# DAMPOWER.net
KiCad netlist of a schematic drawn in EAGLE
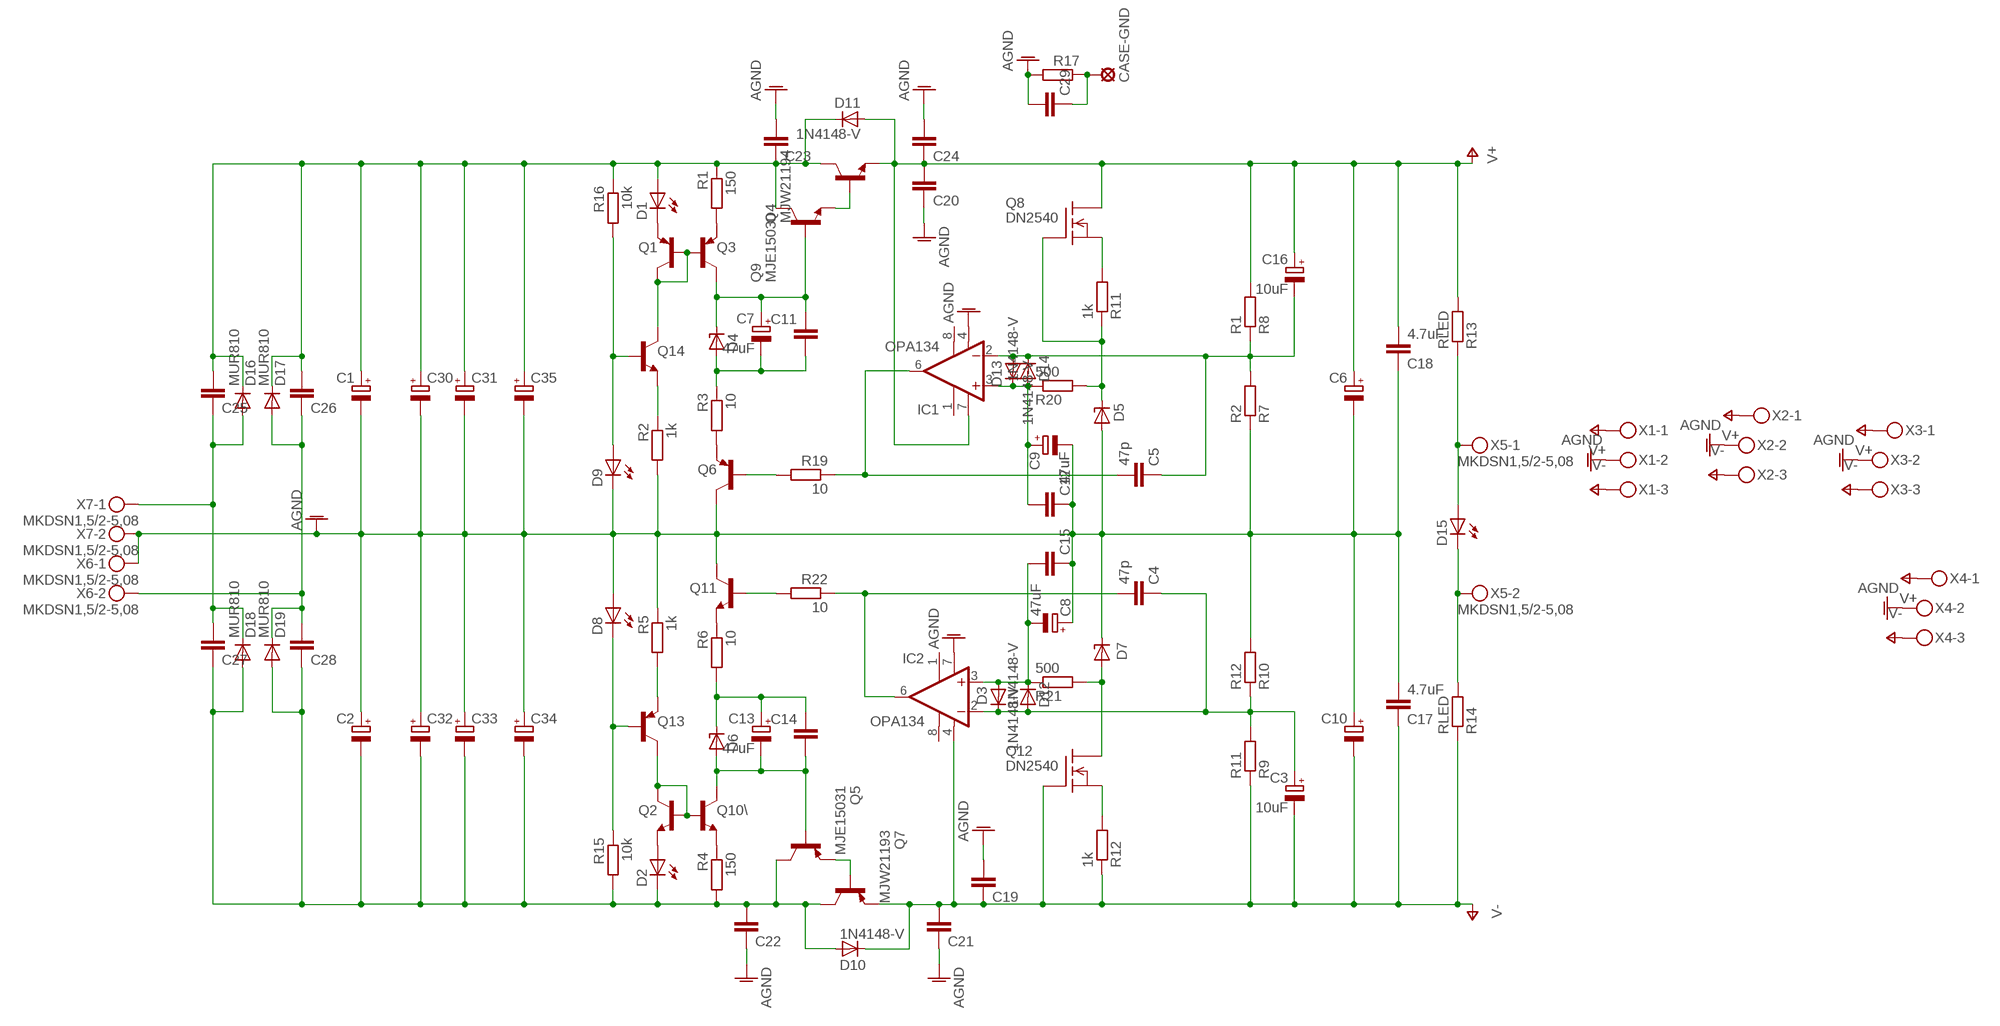
[diagram p0: schematic, sheet 1]
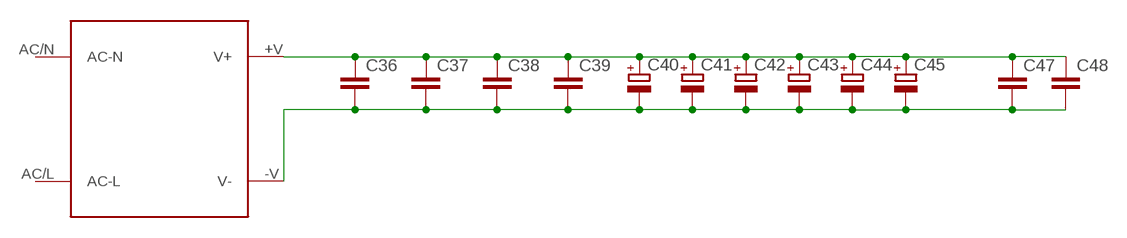
[diagram p1: schematic, sheet 2]
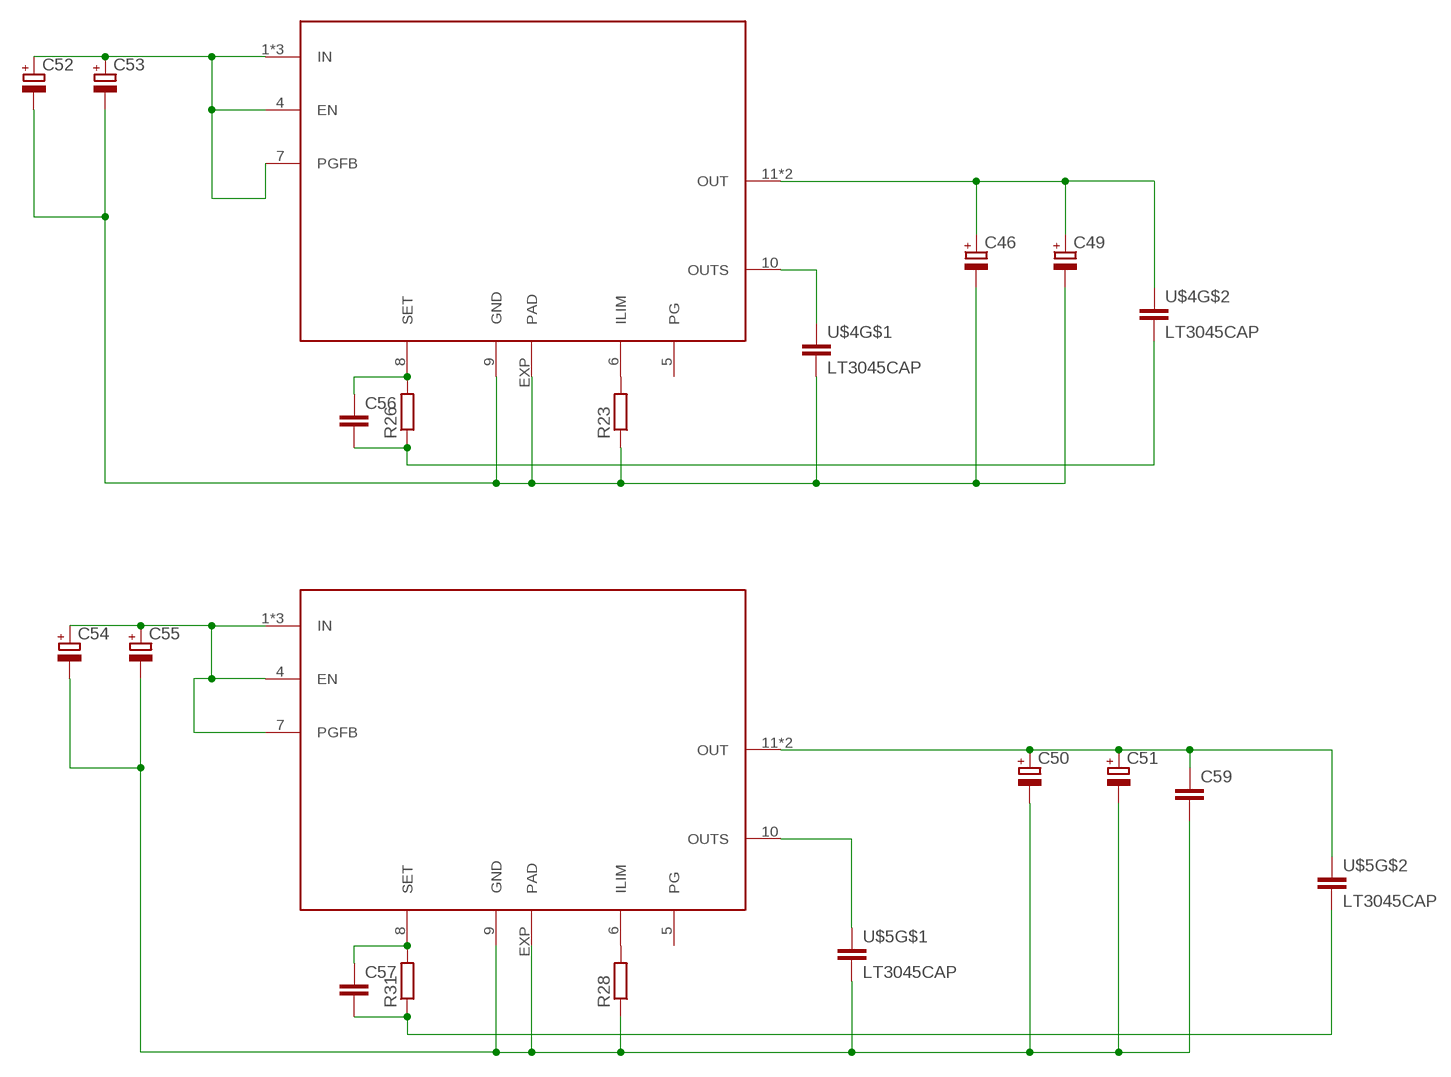
[diagram p2: schematic, sheet 3]

(export (version "E")
  (design (tool "Eeschema 10.0.6"))
  (components
    (comp (ref "C1")
      (value "CPOL-EUE10-35")
      (footprint "eagle-import:EB35D")
      (libsource (lib "eagle-import") (part "CPOL-EUE10-35"))
    )
    (comp (ref "C2")
      (value "CPOL-EUE10-35")
      (footprint "eagle-import:EB35D")
      (libsource (lib "eagle-import") (part "CPOL-EUE10-35"))
    )
    (comp (ref "C3")
      (value "10uF")
      (footprint "eagle-import:E5-8,5")
      (libsource (lib "eagle-import") (part "CPOL-EUE5-8.5"))
    )
    (comp (ref "C4")
      (value "47p")
      (footprint "eagle-import:C025_050-025X075")
      (libsource (lib "eagle-import") (part "C-EU025_050-025X075"))
    )
    (comp (ref "C5")
      (value "47p")
      (footprint "eagle-import:C025_050-025X075")
      (libsource (lib "eagle-import") (part "C-EU025_050-025X075"))
    )
    (comp (ref "C6")
      (value "CPOL-EUE7.5-18")
      (footprint "eagle-import:E7,5-18")
      (libsource (lib "eagle-import") (part "CPOL-EUE7.5-18"))
    )
    (comp (ref "C7")
      (value "47uF")
      (footprint "eagle-import:E5-8,5")
      (libsource (lib "eagle-import") (part "CPOL-EUE5-8.5"))
    )
    (comp (ref "C8")
      (value "47uF")
      (footprint "eagle-import:E5-8,5")
      (libsource (lib "eagle-import") (part "CPOL-EUE5-8.5"))
    )
    (comp (ref "C9")
      (value "47uF")
      (footprint "eagle-import:E5-8,5")
      (libsource (lib "eagle-import") (part "CPOL-EUE5-8.5"))
    )
    (comp (ref "C10")
      (value "CPOL-EUE7.5-18")
      (footprint "eagle-import:E7,5-18")
      (libsource (lib "eagle-import") (part "CPOL-EUE7.5-18"))
    )
    (comp (ref "C11")
      (value "C-EU050-035X075")
      (footprint "eagle-import:C050-035X075")
      (libsource (lib "eagle-import") (part "C-EU050-035X075"))
    )
    (comp (ref "C12")
      (value "C-EU050-035X075")
      (footprint "eagle-import:C050-035X075")
      (libsource (lib "eagle-import") (part "C-EU050-035X075"))
    )
    (comp (ref "C13")
      (value "47uF")
      (footprint "eagle-import:E5-8,5")
      (libsource (lib "eagle-import") (part "CPOL-EUE5-8.5"))
    )
    (comp (ref "C14")
      (value "C-EU050-035X075")
      (footprint "eagle-import:C050-035X075")
      (libsource (lib "eagle-import") (part "C-EU050-035X075"))
    )
    (comp (ref "C15")
      (value "C-EU050-035X075")
      (footprint "eagle-import:C050-035X075")
      (libsource (lib "eagle-import") (part "C-EU050-035X075"))
    )
    (comp (ref "C16")
      (value "10uF")
      (footprint "eagle-import:E5-8,5")
      (libsource (lib "eagle-import") (part "CPOL-EUE5-8.5"))
    )
    (comp (ref "C17")
      (value "4.7uF")
      (footprint "eagle-import:C050-075X075")
      (libsource (lib "eagle-import") (part "C-EU050-075X075"))
    )
    (comp (ref "C18")
      (value "4.7uF")
      (footprint "eagle-import:C050-075X075")
      (libsource (lib "eagle-import") (part "C-EU050-075X075"))
    )
    (comp (ref "C19")
      (value "C-EU050-035X075")
      (footprint "eagle-import:C050-035X075")
      (libsource (lib "eagle-import") (part "C-EU050-035X075"))
    )
    (comp (ref "C20")
      (value "C-EU050-035X075")
      (footprint "eagle-import:C050-035X075")
      (libsource (lib "eagle-import") (part "C-EU050-035X075"))
    )
    (comp (ref "C21")
      (value "C-EU050-035X075")
      (footprint "eagle-import:C050-035X075")
      (libsource (lib "eagle-import") (part "C-EU050-035X075"))
    )
    (comp (ref "C22")
      (value "C-EU050-075X075")
      (footprint "eagle-import:C050-075X075")
      (libsource (lib "eagle-import") (part "C-EU050-075X075"))
    )
    (comp (ref "C23")
      (value "C-EU050-075X075")
      (footprint "eagle-import:C050-075X075")
      (libsource (lib "eagle-import") (part "C-EU050-075X075"))
    )
    (comp (ref "C24")
      (value "C-EU050-035X075")
      (footprint "eagle-import:C050-035X075")
      (libsource (lib "eagle-import") (part "C-EU050-035X075"))
    )
    (comp (ref "C25")
      (value "C-EU050-035X075")
      (footprint "eagle-import:C050-035X075")
      (libsource (lib "eagle-import") (part "C-EU050-035X075"))
    )
    (comp (ref "C26")
      (value "C-EU050-035X075")
      (footprint "eagle-import:C050-035X075")
      (libsource (lib "eagle-import") (part "C-EU050-035X075"))
    )
    (comp (ref "C27")
      (value "C-EU050-035X075")
      (footprint "eagle-import:C050-035X075")
      (libsource (lib "eagle-import") (part "C-EU050-035X075"))
    )
    (comp (ref "C28")
      (value "C-EU050-035X075")
      (footprint "eagle-import:C050-035X075")
      (libsource (lib "eagle-import") (part "C-EU050-035X075"))
    )
    (comp (ref "C29")
      (value "C-EU102_152-062X184")
      (footprint "eagle-import:C102_152-062X184")
      (libsource (lib "eagle-import") (part "C-EU102_152-062X184"))
    )
    (comp (ref "C30")
      (value "CPOL-EUE7.5-18")
      (footprint "eagle-import:E7,5-18")
      (libsource (lib "eagle-import") (part "CPOL-EUE7.5-18"))
    )
    (comp (ref "C31")
      (value "CPOL-EUE7.5-18")
      (footprint "eagle-import:E7,5-18")
      (libsource (lib "eagle-import") (part "CPOL-EUE7.5-18"))
    )
    (comp (ref "C32")
      (value "CPOL-EUE7.5-18")
      (footprint "eagle-import:E7,5-18")
      (libsource (lib "eagle-import") (part "CPOL-EUE7.5-18"))
    )
    (comp (ref "C33")
      (value "CPOL-EUE7.5-18")
      (footprint "eagle-import:E7,5-18")
      (libsource (lib "eagle-import") (part "CPOL-EUE7.5-18"))
    )
    (comp (ref "C34")
      (value "CPOL-EUE7.5-18")
      (footprint "eagle-import:E7,5-18")
      (libsource (lib "eagle-import") (part "CPOL-EUE7.5-18"))
    )
    (comp (ref "C35")
      (value "CPOL-EUE7.5-18")
      (footprint "eagle-import:E7,5-18")
      (libsource (lib "eagle-import") (part "CPOL-EUE7.5-18"))
    )
    (comp (ref "CASE-GND")
      (value "SE14")
      (footprint "eagle-import:SE14")
      (libsource (lib "eagle-import") (part "SE14"))
    )
    (comp (ref "D1")
      (value "LED5MM")
      (footprint "eagle-import:LED5MM")
      (libsource (lib "eagle-import") (part "LED5MM"))
    )
    (comp (ref "D2")
      (value "LED5MM")
      (footprint "eagle-import:LED5MM")
      (libsource (lib "eagle-import") (part "LED5MM"))
    )
    (comp (ref "D3")
      (value "1N4148-V")
      (footprint "eagle-import:1N4148")
      (libsource (lib "eagle-import") (part "1N4148-V"))
    )
    (comp (ref "D4")
      (value "1N4728")
      (footprint "eagle-import:DO41Z10")
      (libsource (lib "eagle-import") (part "1N4728"))
    )
    (comp (ref "D5")
      (value "LT1021")
      (footprint "eagle-import:DIL08")
      (libsource (lib "eagle-import") (part "LT1021-V"))
    )
    (comp (ref "D6")
      (value "1N4728")
      (footprint "eagle-import:DO41Z10")
      (libsource (lib "eagle-import") (part "1N4728"))
    )
    (comp (ref "D7")
      (value "LT1021")
      (footprint "eagle-import:DIL08")
      (libsource (lib "eagle-import") (part "LT1021-V"))
    )
    (comp (ref "D8")
      (value "LED5MM")
      (footprint "eagle-import:LED5MM")
      (libsource (lib "eagle-import") (part "LED5MM"))
    )
    (comp (ref "D9")
      (value "LED5MM")
      (footprint "eagle-import:LED5MM")
      (libsource (lib "eagle-import") (part "LED5MM"))
    )
    (comp (ref "D10")
      (value "1N4148-V")
      (footprint "eagle-import:1N4148")
      (libsource (lib "eagle-import") (part "1N4148-V"))
    )
    (comp (ref "D11")
      (value "1N4148-V")
      (footprint "eagle-import:1N4148")
      (libsource (lib "eagle-import") (part "1N4148-V"))
    )
    (comp (ref "D12")
      (value "1N4148-V")
      (footprint "eagle-import:1N4148")
      (libsource (lib "eagle-import") (part "1N4148-V"))
    )
    (comp (ref "D13")
      (value "1N4148-V")
      (footprint "eagle-import:1N4148")
      (libsource (lib "eagle-import") (part "1N4148-V"))
    )
    (comp (ref "D14")
      (value "1N4148-V")
      (footprint "eagle-import:1N4148")
      (libsource (lib "eagle-import") (part "1N4148-V"))
    )
    (comp (ref "D15")
      (value "LED5MM")
      (footprint "eagle-import:LED5MM")
      (libsource (lib "eagle-import") (part "LED5MM"))
    )
    (comp (ref "D16")
      (value "MUR810")
      (footprint "eagle-import:TO220ACS")
      (libsource (lib "eagle-import") (part "MUR810"))
    )
    (comp (ref "D17")
      (value "MUR810")
      (footprint "eagle-import:TO220ACS")
      (libsource (lib "eagle-import") (part "MUR810"))
    )
    (comp (ref "D18")
      (value "MUR810")
      (footprint "eagle-import:TO220ACS")
      (libsource (lib "eagle-import") (part "MUR810"))
    )
    (comp (ref "D19")
      (value "MUR810")
      (footprint "eagle-import:TO220ACS")
      (libsource (lib "eagle-import") (part "MUR810"))
    )
    (comp (ref "IC1")
      (value "OPA134")
      (footprint "eagle-import:DIL08")
      (fields (field (name "MF") "TEXAS INSTRUMENTS") (field (name "MPN") "OPA134PA"))
      (libsource (lib "eagle-import") (part "OPA134P"))
    )
    (comp (ref "IC2")
      (value "OPA134")
      (footprint "eagle-import:DIL08")
      (fields (field (name "MF") "TEXAS INSTRUMENTS") (field (name "MPN") "OPA134PA"))
      (libsource (lib "eagle-import") (part "OPA134P"))
    )
    (comp (ref "Q1")
      (value "MPSA92-PNP-TO92-EBC")
      (footprint "eagle-import:TO92-EBC")
      (libsource (lib "eagle-import") (part "-PNP-TO92-EBCMPSA92"))
    )
    (comp (ref "Q2")
      (value "MPSA42-NPN-TO92-EBC")
      (footprint "eagle-import:TO92-EBC")
      (libsource (lib "eagle-import") (part "-NPN-TO92-EBCMPSA42"))
    )
    (comp (ref "Q3")
      (value "MPSA92-PNP-TO92-EBC")
      (footprint "eagle-import:TO92-EBC")
      (libsource (lib "eagle-import") (part "-PNP-TO92-EBCMPSA92"))
    )
    (comp (ref "Q4")
      (value "MJW21194")
      (footprint "eagle-import:TO-264")
      (libsource (lib "eagle-import") (part "MJL4281"))
    )
    (comp (ref "Q5")
      (value "MJE15031")
      (footprint "eagle-import:TO220KG")
      (libsource (lib "eagle-import") (part "MJE15031"))
    )
    (comp (ref "Q6")
      (value "MPSA92-PNP-TO92-EBC")
      (footprint "eagle-import:TO92-EBC")
      (libsource (lib "eagle-import") (part "-PNP-TO92-EBCMPSA92"))
    )
    (comp (ref "Q7")
      (value "MJW21193")
      (footprint "eagle-import:TO-264")
      (libsource (lib "eagle-import") (part "MJL4302"))
    )
    (comp (ref "Q8")
      (value "DN2540")
      (footprint "eagle-import:TO92-")
      (libsource (lib "eagle-import") (part "2N7000"))
    )
    (comp (ref "Q9")
      (value "MJE15030")
      (footprint "eagle-import:TO220KG")
      (libsource (lib "eagle-import") (part "MJE15030"))
    )
    (comp (ref "Q10\\")
      (value "MPSA42-NPN-TO92-EBC")
      (footprint "eagle-import:TO92-EBC")
      (libsource (lib "eagle-import") (part "-NPN-TO92-EBCMPSA42"))
    )
    (comp (ref "Q11")
      (value "MPSA42-NPN-TO92-EBC")
      (footprint "eagle-import:TO92-EBC")
      (libsource (lib "eagle-import") (part "-NPN-TO92-EBCMPSA42"))
    )
    (comp (ref "Q12")
      (value "DN2540")
      (footprint "eagle-import:TO92-")
      (libsource (lib "eagle-import") (part "2N7000"))
    )
    (comp (ref "Q13")
      (value "MPSA92-PNP-TO92-EBC")
      (footprint "eagle-import:TO92-EBC")
      (libsource (lib "eagle-import") (part "-PNP-TO92-EBCMPSA92"))
    )
    (comp (ref "Q14")
      (value "MPSA42-NPN-TO92-EBC")
      (footprint "eagle-import:TO92-EBC")
      (libsource (lib "eagle-import") (part "-NPN-TO92-EBCMPSA42"))
    )
    (comp (ref "R1")
      (value "150")
      (footprint "eagle-import:0309_12")
      (libsource (lib "eagle-import") (part "R-EU_0309/12"))
    )
    (comp (ref "R2")
      (value "1k")
      (footprint "eagle-import:0309_12")
      (libsource (lib "eagle-import") (part "R-EU_0309/12"))
    )
    (comp (ref "R3")
      (value "10")
      (footprint "eagle-import:0309_12")
      (libsource (lib "eagle-import") (part "R-EU_0309/12"))
    )
    (comp (ref "R4")
      (value "150")
      (footprint "eagle-import:0309_12")
      (libsource (lib "eagle-import") (part "R-EU_0309/12"))
    )
    (comp (ref "R5")
      (value "1k")
      (footprint "eagle-import:0309_12")
      (libsource (lib "eagle-import") (part "R-EU_0309/12"))
    )
    (comp (ref "R6")
      (value "10")
      (footprint "eagle-import:0309_12")
      (libsource (lib "eagle-import") (part "R-EU_0309/12"))
    )
    (comp (ref "R7")
      (value "R2")
      (footprint "eagle-import:0309_12")
      (libsource (lib "eagle-import") (part "R-EU_0309/12"))
    )
    (comp (ref "R8")
      (value "R1")
      (footprint "eagle-import:0309_12")
      (libsource (lib "eagle-import") (part "R-EU_0309/12"))
    )
    (comp (ref "R9")
      (value "R11")
      (footprint "eagle-import:0309_12")
      (libsource (lib "eagle-import") (part "R-EU_0309/12"))
    )
    (comp (ref "R10")
      (value "R12")
      (footprint "eagle-import:0309_12")
      (libsource (lib "eagle-import") (part "R-EU_0309/12"))
    )
    (comp (ref "R11")
      (value "1k")
      (footprint "eagle-import:0309_12")
      (libsource (lib "eagle-import") (part "R-EU_0309/12"))
    )
    (comp (ref "R12")
      (value "1k")
      (footprint "eagle-import:0309_12")
      (libsource (lib "eagle-import") (part "R-EU_0309/12"))
    )
    (comp (ref "R13")
      (value "RLED")
      (footprint "eagle-import:0309_12")
      (libsource (lib "eagle-import") (part "R-EU_0309/12"))
    )
    (comp (ref "R14")
      (value "RLED")
      (footprint "eagle-import:0309_12")
      (libsource (lib "eagle-import") (part "R-EU_0309/12"))
    )
    (comp (ref "R15")
      (value "10k")
      (footprint "eagle-import:0309_12")
      (libsource (lib "eagle-import") (part "R-EU_0309/12"))
    )
    (comp (ref "R16")
      (value "10k")
      (footprint "eagle-import:0309_12")
      (libsource (lib "eagle-import") (part "R-EU_0309/12"))
    )
    (comp (ref "R17")
      (value "R-EU_0617/22")
      (footprint "eagle-import:0617_22")
      (libsource (lib "eagle-import") (part "R-EU_0617/22"))
    )
    (comp (ref "R19")
      (value "10")
      (footprint "eagle-import:0309_12")
      (libsource (lib "eagle-import") (part "R-EU_0309/12"))
    )
    (comp (ref "R20")
      (value "500")
      (footprint "eagle-import:0309_12")
      (libsource (lib "eagle-import") (part "R-EU_0309/12"))
    )
    (comp (ref "R21")
      (value "500")
      (footprint "eagle-import:0309_12")
      (libsource (lib "eagle-import") (part "R-EU_0309/12"))
    )
    (comp (ref "R22")
      (value "10")
      (footprint "eagle-import:0309_12")
      (libsource (lib "eagle-import") (part "R-EU_0309/12"))
    )
    (comp (ref "X1")
      (value "MKDSN1,5/3-5,08")
      (footprint "eagle-import:MKDSN1,5_3-5,08")
      (libsource (lib "eagle-import") (part "MKDSN1,5/3-5,08"))
    )
    (comp (ref "X2")
      (value "MKDSN1,5/3-5,08")
      (footprint "eagle-import:MKDSN1,5_3-5,08")
      (libsource (lib "eagle-import") (part "MKDSN1,5/3-5,08"))
    )
    (comp (ref "X3")
      (value "MKDSN1,5/3-5,08")
      (footprint "eagle-import:MKDSN1,5_3-5,08")
      (libsource (lib "eagle-import") (part "MKDSN1,5/3-5,08"))
    )
    (comp (ref "X4")
      (value "MKDSN1,5/3-5,08")
      (footprint "eagle-import:MKDSN1,5_3-5,08")
      (libsource (lib "eagle-import") (part "MKDSN1,5/3-5,08"))
    )
    (comp (ref "X5")
      (value "MKDSN1,5/2-5,08")
      (footprint "eagle-import:MKDSN1,5_2-5,08")
      (libsource (lib "eagle-import") (part "MKDSN1,5/2-5,08"))
    )
    (comp (ref "X6")
      (value "MKDSN1,5/2-5,08")
      (footprint "eagle-import:MKDSN1,5_2-5,08")
      (libsource (lib "eagle-import") (part "MKDSN1,5/2-5,08"))
    )
    (comp (ref "X7")
      (value "MKDSN1,5/2-5,08")
      (footprint "eagle-import:MKDSN1,5_2-5,08")
      (libsource (lib "eagle-import") (part "MKDSN1,5/2-5,08"))
    )
    (comp (ref "C36")
      (value "C-EU050-030X075")
      (footprint "eagle-import:C050-030X075")
      (libsource (lib "eagle-import") (part "C-EU050-030X075"))
    )
    (comp (ref "C37")
      (value "C-EU050-030X075")
      (footprint "eagle-import:C050-030X075")
      (libsource (lib "eagle-import") (part "C-EU050-030X075"))
    )
    (comp (ref "C38")
      (value "C-EU050-030X075")
      (footprint "eagle-import:C050-030X075")
      (libsource (lib "eagle-import") (part "C-EU050-030X075"))
    )
    (comp (ref "C39")
      (value "C-EU050-030X075")
      (footprint "eagle-import:C050-030X075")
      (libsource (lib "eagle-import") (part "C-EU050-030X075"))
    )
    (comp (ref "C40")
      (value "CPOL-EUE3.5-8")
      (footprint "eagle-import:E3,5-8")
      (libsource (lib "eagle-import") (part "CPOL-EUE3.5-8"))
    )
    (comp (ref "C41")
      (value "CPOL-EUE3.5-8")
      (footprint "eagle-import:E3,5-8")
      (libsource (lib "eagle-import") (part "CPOL-EUE3.5-8"))
    )
    (comp (ref "C42")
      (value "CPOL-EUE3.5-8")
      (footprint "eagle-import:E3,5-8")
      (libsource (lib "eagle-import") (part "CPOL-EUE3.5-8"))
    )
    (comp (ref "C43")
      (value "CPOL-EUE3.5-8")
      (footprint "eagle-import:E3,5-8")
      (libsource (lib "eagle-import") (part "CPOL-EUE3.5-8"))
    )
    (comp (ref "C44")
      (value "CPOL-EUE3.5-8")
      (footprint "eagle-import:E3,5-8")
      (libsource (lib "eagle-import") (part "CPOL-EUE3.5-8"))
    )
    (comp (ref "C45")
      (value "CPOL-EUE3.5-8")
      (footprint "eagle-import:E3,5-8")
      (libsource (lib "eagle-import") (part "CPOL-EUE3.5-8"))
    )
    (comp (ref "C47")
      (value "C-EU050-030X075")
      (footprint "eagle-import:C050-030X075")
      (libsource (lib "eagle-import") (part "C-EU050-030X075"))
    )
    (comp (ref "C48")
      (value "C-EU050-030X075")
      (footprint "eagle-import:C050-030X075")
      (libsource (lib "eagle-import") (part "C-EU050-030X075"))
    )
    (comp (ref "U$1")
      (value "IRM-15-5")
      (footprint "eagle-import:IRM-15")
      (libsource (lib "eagle-import") (part "IRM-15-5"))
    )
    (comp (ref "C46")
      (value "CPOL-EUE3.5-8")
      (footprint "eagle-import:E3,5-8")
      (libsource (lib "eagle-import") (part "CPOL-EUE3.5-8"))
    )
    (comp (ref "C49")
      (value "CPOL-EUE3.5-8")
      (footprint "eagle-import:E3,5-8")
      (libsource (lib "eagle-import") (part "CPOL-EUE3.5-8"))
    )
    (comp (ref "C50")
      (value "CPOL-EUE3.5-8")
      (footprint "eagle-import:E3,5-8")
      (libsource (lib "eagle-import") (part "CPOL-EUE3.5-8"))
    )
    (comp (ref "C51")
      (value "CPOL-EUE3.5-8")
      (footprint "eagle-import:E3,5-8")
      (libsource (lib "eagle-import") (part "CPOL-EUE3.5-8"))
    )
    (comp (ref "C52")
      (value "CPOL-EUE5-10.5")
      (footprint "eagle-import:E5-10,5")
      (libsource (lib "eagle-import") (part "CPOL-EUE5-10.5"))
    )
    (comp (ref "C53")
      (value "CPOL-EUE5-10.5")
      (footprint "eagle-import:E5-10,5")
      (libsource (lib "eagle-import") (part "CPOL-EUE5-10.5"))
    )
    (comp (ref "C54")
      (value "CPOL-EUE5-10.5")
      (footprint "eagle-import:E5-10,5")
      (libsource (lib "eagle-import") (part "CPOL-EUE5-10.5"))
    )
    (comp (ref "C55")
      (value "CPOL-EUE5-10.5")
      (footprint "eagle-import:E5-10,5")
      (libsource (lib "eagle-import") (part "CPOL-EUE5-10.5"))
    )
    (comp (ref "C56")
      (value "C-EUC1210")
      (footprint "eagle-import:C1210")
      (libsource (lib "eagle-import") (part "C-EUC1210"))
    )
    (comp (ref "C57")
      (value "C-EUC1210")
      (footprint "eagle-import:C1210")
      (libsource (lib "eagle-import") (part "C-EUC1210"))
    )
    (comp (ref "C59")
      (value "C-EUC1210")
      (footprint "eagle-import:C1210")
      (libsource (lib "eagle-import") (part "C-EUC1210"))
    )
    (comp (ref "R23")
      (value "R-EU_MELF0204R")
      (footprint "eagle-import:MINI_MELF-0204R")
      (libsource (lib "eagle-import") (part "R-EU_MELF0204R"))
    )
    (comp (ref "R26")
      (value "R-EU_MELF0204R")
      (footprint "eagle-import:MINI_MELF-0204R")
      (libsource (lib "eagle-import") (part "R-EU_MELF0204R"))
    )
    (comp (ref "R28")
      (value "R-EU_MELF0204R")
      (footprint "eagle-import:MINI_MELF-0204R")
      (libsource (lib "eagle-import") (part "R-EU_MELF0204R"))
    )
    (comp (ref "R31")
      (value "R-EU_MELF0204R")
      (footprint "eagle-import:MINI_MELF-0204R")
      (libsource (lib "eagle-import") (part "R-EU_MELF0204R"))
    )
    (comp (ref "U$2")
      (value "LT3045")
      (footprint "eagle-import:MSOP12")
      (libsource (lib "eagle-import") (part "LT3045"))
    )
    (comp (ref "U$3")
      (value "LT3045")
      (footprint "eagle-import:MSOP12")
      (libsource (lib "eagle-import") (part "LT3045"))
    )
    (comp (ref "U$4")
      (value "LT3045CAP")
      (footprint "eagle-import:LT3045CAP")
      (libsource (lib "eagle-import") (part "LT3045CAP"))
    )
    (comp (ref "U$5")
      (value "LT3045CAP")
      (footprint "eagle-import:LT3045CAP")
      (libsource (lib "eagle-import") (part "LT3045CAP"))
    )
  )
  (nets
    (net (code "1") (name "AGND") (class "Default")
      (node (ref "C1") (pin "-") (pinfunction "-_-") (pintype "passive"))
      (node (ref "C10") (pin "+") (pinfunction "+_+") (pintype "passive"))
      (node (ref "C12") (pin "1") (pinfunction "1_1") (pintype "passive"))
      (node (ref "C15") (pin "1") (pinfunction "1_1") (pintype "passive"))
      (node (ref "C17") (pin "2") (pinfunction "2_2") (pintype "passive"))
      (node (ref "C18") (pin "1") (pinfunction "1_1") (pintype "passive"))
      (node (ref "C19") (pin "2") (pinfunction "2_2") (pintype "passive"))
      (node (ref "C2") (pin "+") (pinfunction "+_+") (pintype "passive"))
      (node (ref "C20") (pin "1") (pinfunction "1_1") (pintype "passive"))
      (node (ref "C21") (pin "1") (pinfunction "1_1") (pintype "passive"))
      (node (ref "C22") (pin "1") (pinfunction "1_1") (pintype "passive"))
      (node (ref "C23") (pin "2") (pinfunction "2_2") (pintype "passive"))
      (node (ref "C24") (pin "2") (pinfunction "2_2") (pintype "passive"))
      (node (ref "C29") (pin "2") (pinfunction "2_2") (pintype "passive"))
      (node (ref "C29") (pin "3") (pinfunction "2_3") (pintype "passive"))
      (node (ref "C30") (pin "-") (pinfunction "-_-") (pintype "passive"))
      (node (ref "C31") (pin "-") (pinfunction "-_-") (pintype "passive"))
      (node (ref "C32") (pin "+") (pinfunction "+_+") (pintype "passive"))
      (node (ref "C33") (pin "+") (pinfunction "+_+") (pintype "passive"))
      (node (ref "C34") (pin "+") (pinfunction "+_+") (pintype "passive"))
      (node (ref "C35") (pin "-") (pinfunction "-_-") (pintype "passive"))
      (node (ref "C6") (pin "-") (pinfunction "-_-") (pintype "passive"))
      (node (ref "C8") (pin "+") (pinfunction "+_+") (pintype "passive"))
      (node (ref "C9") (pin "-") (pinfunction "-_-") (pintype "passive"))
      (node (ref "D5") (pin "4") (pinfunction "GND_4") (pintype "passive"))
      (node (ref "D7") (pin "6") (pinfunction "OUT_6") (pintype "passive"))
      (node (ref "D8") (pin "A") (pinfunction "A_A") (pintype "passive"))
      (node (ref "D9") (pin "K") (pinfunction "C_K") (pintype "passive"))
      (node (ref "IC1") (pin "4") (pinfunction "V-_4") (pintype "power_in"))
      (node (ref "IC2") (pin "7") (pinfunction "V+_7") (pintype "power_in"))
      (node (ref "Q11") (pin "C") (pinfunction "C_C") (pintype "passive"))
      (node (ref "Q6") (pin "C") (pinfunction "C_C") (pintype "passive"))
      (node (ref "R10") (pin "2") (pinfunction "2_2") (pintype "passive"))
      (node (ref "R17") (pin "2") (pinfunction "2_2") (pintype "passive"))
      (node (ref "R2") (pin "2") (pinfunction "2_2") (pintype "passive"))
      (node (ref "R5") (pin "1") (pinfunction "1_1") (pintype "passive"))
      (node (ref "R7") (pin "1") (pinfunction "1_1") (pintype "passive"))
      (node (ref "X1") (pin "2") (pinfunction "KL_2") (pintype "passive"))
      (node (ref "X2") (pin "2") (pinfunction "KL_2") (pintype "passive"))
      (node (ref "X3") (pin "2") (pinfunction "KL_2") (pintype "passive"))
      (node (ref "X4") (pin "2") (pinfunction "KL_2") (pintype "passive"))
      (node (ref "X6") (pin "1") (pinfunction "KL_1") (pintype "passive"))
      (node (ref "X7") (pin "2") (pinfunction "KL_2") (pintype "passive"))
    )
    (net (code "2") (name "Net-(C11-Pad2)") (class "Default")
      (node (ref "C11") (pin "2") (pinfunction "2_2") (pintype "passive"))
      (node (ref "C7") (pin "-") (pinfunction "-_-") (pintype "passive"))
      (node (ref "D4") (pin "A") (pinfunction "A_A") (pintype "passive"))
      (node (ref "R3") (pin "1") (pinfunction "1_1") (pintype "passive"))
    )
    (net (code "3") (name "Net-(C13-Pad+)") (class "Default")
      (node (ref "C13") (pin "+") (pinfunction "+_+") (pintype "passive"))
      (node (ref "C14") (pin "1") (pinfunction "1_1") (pintype "passive"))
      (node (ref "D6") (pin "C") (pinfunction "C_C") (pintype "passive"))
      (node (ref "R6") (pin "2") (pinfunction "2_2") (pintype "passive"))
    )
    (net (code "4") (name "Net-(C29-Pad1)") (class "Default")
      (node (ref "C29") (pin "1") (pinfunction "1_1") (pintype "passive"))
      (node (ref "CASE-GND") (pin "MP") (pinfunction "MP_MP") (pintype "passive"))
      (node (ref "R17") (pin "1") (pinfunction "1_1") (pintype "passive"))
    )
    (net (code "5") (name "Net-(D1-C)") (class "Default")
      (node (ref "D1") (pin "K") (pinfunction "C_K") (pintype "passive"))
      (node (ref "Q1") (pin "E") (pinfunction "E_E") (pintype "passive"))
    )
    (net (code "6") (name "Net-(D2-C)") (class "Default")
      (node (ref "C2") (pin "-") (pinfunction "-_-") (pintype "passive"))
      (node (ref "C22") (pin "2") (pinfunction "2_2") (pintype "passive"))
      (node (ref "C27") (pin "1") (pinfunction "1_1") (pintype "passive"))
      (node (ref "C28") (pin "1") (pinfunction "1_1") (pintype "passive"))
      (node (ref "C32") (pin "-") (pinfunction "-_-") (pintype "passive"))
      (node (ref "C33") (pin "-") (pinfunction "-_-") (pintype "passive"))
      (node (ref "C34") (pin "-") (pinfunction "-_-") (pintype "passive"))
      (node (ref "D10") (pin "A") (pinfunction "A_A") (pintype "passive"))
      (node (ref "D18") (pin "A") (pinfunction "A_A") (pintype "passive"))
      (node (ref "D19") (pin "A") (pinfunction "A_A") (pintype "passive"))
      (node (ref "D2") (pin "K") (pinfunction "C_K") (pintype "passive"))
      (node (ref "Q5") (pin "2") (pinfunction "C_2") (pintype "passive"))
      (node (ref "Q7") (pin "C") (pinfunction "C_C") (pintype "passive"))
      (node (ref "R15") (pin "2") (pinfunction "2_2") (pintype "passive"))
      (node (ref "R4") (pin "2") (pinfunction "2_2") (pintype "passive"))
    )
    (net (code "7") (name "Net-(D2-PadA)") (class "Default")
      (node (ref "D2") (pin "A") (pinfunction "A_A") (pintype "passive"))
      (node (ref "Q2") (pin "E") (pinfunction "E_E") (pintype "passive"))
    )
    (net (code "8") (name "Net-(D5-OUT)") (class "Default")
      (node (ref "D5") (pin "6") (pinfunction "OUT_6") (pintype "passive"))
      (node (ref "Q8") (pin "2") (pinfunction "G_2") (pintype "passive"))
      (node (ref "R11") (pin "1") (pinfunction "1_1") (pintype "passive"))
      (node (ref "R20") (pin "2") (pinfunction "2_2") (pintype "passive"))
    )
    (net (code "9") (name "Net-(D7-GND)") (class "Default")
      (node (ref "D7") (pin "4") (pinfunction "GND_4") (pintype "passive"))
      (node (ref "Q12") (pin "1") (pinfunction "D_1") (pintype "passive"))
      (node (ref "R21") (pin "2") (pinfunction "2_2") (pintype "passive"))
    )
    (net (code "10") (name "Net-(D8-C)") (class "Default")
      (node (ref "D8") (pin "K") (pinfunction "C_K") (pintype "passive"))
      (node (ref "Q13") (pin "B") (pinfunction "B_B") (pintype "passive"))
      (node (ref "R15") (pin "1") (pinfunction "1_1") (pintype "passive"))
    )
    (net (code "11") (name "Net-(D9-PadA)") (class "Default")
      (node (ref "D9") (pin "A") (pinfunction "A_A") (pintype "passive"))
      (node (ref "Q14") (pin "B") (pinfunction "B_B") (pintype "passive"))
      (node (ref "R16") (pin "2") (pinfunction "2_2") (pintype "passive"))
    )
    (net (code "12") (name "Net-(D15-C)") (class "Default")
      (node (ref "D15") (pin "K") (pinfunction "C_K") (pintype "passive"))
      (node (ref "R14") (pin "2") (pinfunction "2_2") (pintype "passive"))
      (node (ref "X5") (pin "2") (pinfunction "KL_2") (pintype "passive"))
    )
    (net (code "13") (name "Net-(IC1-+IN)") (class "Default")
      (node (ref "C12") (pin "2") (pinfunction "2_2") (pintype "passive"))
      (node (ref "C9") (pin "+") (pinfunction "+_+") (pintype "passive"))
      (node (ref "D13") (pin "C") (pinfunction "C_C") (pintype "passive"))
      (node (ref "D14") (pin "A") (pinfunction "A_A") (pintype "passive"))
      (node (ref "IC1") (pin "3") (pinfunction "+IN_3") (pintype "input"))
      (node (ref "R20") (pin "1") (pinfunction "1_1") (pintype "passive"))
    )
    (net (code "14") (name "Net-(IC1--IN)") (class "Default")
      (node (ref "C16") (pin "-") (pinfunction "-_-") (pintype "passive"))
      (node (ref "C5") (pin "1") (pinfunction "1_1") (pintype "passive"))
      (node (ref "D13") (pin "A") (pinfunction "A_A") (pintype "passive"))
      (node (ref "D14") (pin "C") (pinfunction "C_C") (pintype "passive"))
      (node (ref "IC1") (pin "2") (pinfunction "-IN_2") (pintype "input"))
      (node (ref "R7") (pin "2") (pinfunction "2_2") (pintype "passive"))
      (node (ref "R8") (pin "1") (pinfunction "1_1") (pintype "passive"))
    )
    (net (code "15") (name "Net-(IC1-OUT)") (class "Default")
      (node (ref "C5") (pin "2") (pinfunction "2_2") (pintype "passive"))
      (node (ref "C5") (pin "3") (pinfunction "2_3") (pintype "passive"))
      (node (ref "IC1") (pin "6") (pinfunction "OUT_6") (pintype "output"))
      (node (ref "R19") (pin "1") (pinfunction "1_1") (pintype "passive"))
    )
    (net (code "16") (name "Net-(IC2-+IN)") (class "Default")
      (node (ref "C15") (pin "2") (pinfunction "2_2") (pintype "passive"))
      (node (ref "C8") (pin "-") (pinfunction "-_-") (pintype "passive"))
      (node (ref "D12") (pin "C") (pinfunction "C_C") (pintype "passive"))
      (node (ref "D3") (pin "A") (pinfunction "A_A") (pintype "passive"))
      (node (ref "IC2") (pin "3") (pinfunction "+IN_3") (pintype "input"))
      (node (ref "R21") (pin "1") (pinfunction "1_1") (pintype "passive"))
    )
    (net (code "17") (name "Net-(IC2--IN)") (class "Default")
      (node (ref "C3") (pin "+") (pinfunction "+_+") (pintype "passive"))
      (node (ref "C4") (pin "1") (pinfunction "1_1") (pintype "passive"))
      (node (ref "D12") (pin "A") (pinfunction "A_A") (pintype "passive"))
      (node (ref "D3") (pin "C") (pinfunction "C_C") (pintype "passive"))
      (node (ref "IC2") (pin "2") (pinfunction "-IN_2") (pintype "input"))
      (node (ref "R10") (pin "1") (pinfunction "1_1") (pintype "passive"))
      (node (ref "R9") (pin "2") (pinfunction "2_2") (pintype "passive"))
    )
    (net (code "18") (name "Net-(IC2-OUT)") (class "Default")
      (node (ref "C4") (pin "2") (pinfunction "2_2") (pintype "passive"))
      (node (ref "C4") (pin "3") (pinfunction "2_3") (pintype "passive"))
      (node (ref "IC2") (pin "6") (pinfunction "OUT_6") (pintype "output"))
      (node (ref "R22") (pin "1") (pinfunction "1_1") (pintype "passive"))
    )
    (net (code "19") (name "Net-(Q1-PadB)") (class "Default")
      (node (ref "Q1") (pin "B") (pinfunction "B_B") (pintype "passive"))
      (node (ref "Q1") (pin "C") (pinfunction "C_C") (pintype "passive"))
      (node (ref "Q14") (pin "C") (pinfunction "C_C") (pintype "passive"))
      (node (ref "Q3") (pin "B") (pinfunction "B_B") (pintype "passive"))
    )
    (net (code "20") (name "Net-(Q3-PadE)") (class "Default")
      (node (ref "Q3") (pin "E") (pinfunction "E_E") (pintype "passive"))
      (node (ref "R1") (pin "2") (pinfunction "2_2") (pintype "passive"))
    )
    (net (code "21") (name "Net-(Q5-B)") (class "Default")
      (node (ref "C13") (pin "-") (pinfunction "-_-") (pintype "passive"))
      (node (ref "C14") (pin "2") (pinfunction "2_2") (pintype "passive"))
      (node (ref "D6") (pin "A") (pinfunction "A_A") (pintype "passive"))
      (node (ref "Q10\\") (pin "C") (pinfunction "C_C") (pintype "passive"))
      (node (ref "Q5") (pin "1") (pinfunction "B_1") (pintype "passive"))
    )
    (net (code "22") (name "Net-(Q5-E)") (class "Default")
      (node (ref "Q5") (pin "3") (pinfunction "E_3") (pintype "passive"))
      (node (ref "Q7") (pin "B") (pinfunction "B_B") (pintype "passive"))
    )
    (net (code "23") (name "Net-(Q6-PadB)") (class "Default")
      (node (ref "Q6") (pin "B") (pinfunction "B_B") (pintype "passive"))
      (node (ref "R19") (pin "2") (pinfunction "2_2") (pintype "passive"))
    )
    (net (code "24") (name "Net-(Q6-PadE)") (class "Default")
      (node (ref "Q6") (pin "E") (pinfunction "E_E") (pintype "passive"))
      (node (ref "R3") (pin "2") (pinfunction "2_2") (pintype "passive"))
    )
    (net (code "25") (name "Net-(Q8-S)") (class "Default")
      (node (ref "Q8") (pin "3") (pinfunction "S_3") (pintype "passive"))
      (node (ref "R11") (pin "2") (pinfunction "2_2") (pintype "passive"))
    )
    (net (code "26") (name "Net-(Q9-B)") (class "Default")
      (node (ref "C11") (pin "1") (pinfunction "1_1") (pintype "passive"))
      (node (ref "C7") (pin "+") (pinfunction "+_+") (pintype "passive"))
      (node (ref "D4") (pin "C") (pinfunction "C_C") (pintype "passive"))
      (node (ref "Q3") (pin "C") (pinfunction "C_C") (pintype "passive"))
      (node (ref "Q9") (pin "1") (pinfunction "B_1") (pintype "passive"))
    )
    (net (code "27") (name "Net-(Q9-C)") (class "Default")
      (node (ref "C1") (pin "+") (pinfunction "+_+") (pintype "passive"))
      (node (ref "C23") (pin "1") (pinfunction "1_1") (pintype "passive"))
      (node (ref "C25") (pin "2") (pinfunction "2_2") (pintype "passive"))
      (node (ref "C26") (pin "2") (pinfunction "2_2") (pintype "passive"))
      (node (ref "C30") (pin "+") (pinfunction "+_+") (pintype "passive"))
      (node (ref "C31") (pin "+") (pinfunction "+_+") (pintype "passive"))
      (node (ref "C35") (pin "+") (pinfunction "+_+") (pintype "passive"))
      (node (ref "D1") (pin "A") (pinfunction "A_A") (pintype "passive"))
      (node (ref "D11") (pin "C") (pinfunction "C_C") (pintype "passive"))
      (node (ref "D16") (pin "C") (pinfunction "C_C") (pintype "passive"))
      (node (ref "D17") (pin "C") (pinfunction "C_C") (pintype "passive"))
      (node (ref "Q4") (pin "C") (pinfunction "C_C") (pintype "passive"))
      (node (ref "Q9") (pin "2") (pinfunction "C_2") (pintype "passive"))
      (node (ref "R1") (pin "1") (pinfunction "1_1") (pintype "passive"))
      (node (ref "R16") (pin "1") (pinfunction "1_1") (pintype "passive"))
    )
    (net (code "28") (name "Net-(Q9-E)") (class "Default")
      (node (ref "Q4") (pin "B") (pinfunction "B_B") (pintype "passive"))
      (node (ref "Q9") (pin "3") (pinfunction "E_3") (pintype "passive"))
    )
    (net (code "29") (name "Net-(Q10\\-PadB)") (class "Default")
      (node (ref "Q10\\") (pin "B") (pinfunction "B_B") (pintype "passive"))
      (node (ref "Q13") (pin "C") (pinfunction "C_C") (pintype "passive"))
      (node (ref "Q2") (pin "B") (pinfunction "B_B") (pintype "passive"))
      (node (ref "Q2") (pin "C") (pinfunction "C_C") (pintype "passive"))
    )
    (net (code "30") (name "Net-(Q10\\-PadE)") (class "Default")
      (node (ref "Q10\\") (pin "E") (pinfunction "E_E") (pintype "passive"))
      (node (ref "R4") (pin "1") (pinfunction "1_1") (pintype "passive"))
    )
    (net (code "31") (name "Net-(Q11-PadB)") (class "Default")
      (node (ref "Q11") (pin "B") (pinfunction "B_B") (pintype "passive"))
      (node (ref "R22") (pin "2") (pinfunction "2_2") (pintype "passive"))
    )
    (net (code "32") (name "Net-(Q11-PadE)") (class "Default")
      (node (ref "Q11") (pin "E") (pinfunction "E_E") (pintype "passive"))
      (node (ref "R6") (pin "1") (pinfunction "1_1") (pintype "passive"))
    )
    (net (code "33") (name "Net-(Q12-S)") (class "Default")
      (node (ref "Q12") (pin "3") (pinfunction "S_3") (pintype "passive"))
      (node (ref "R12") (pin "2") (pinfunction "2_2") (pintype "passive"))
    )
    (net (code "34") (name "Net-(Q13-PadE)") (class "Default")
      (node (ref "Q13") (pin "E") (pinfunction "E_E") (pintype "passive"))
      (node (ref "R5") (pin "2") (pinfunction "2_2") (pintype "passive"))
    )
    (net (code "35") (name "Net-(Q14-PadE)") (class "Default")
      (node (ref "Q14") (pin "E") (pinfunction "E_E") (pintype "passive"))
      (node (ref "R2") (pin "1") (pinfunction "1_1") (pintype "passive"))
    )
    (net (code "36") (name "Net-(U$1-V+)") (class "Default")
      (node (ref "C36") (pin "1") (pinfunction "1_1") (pintype "passive"))
      (node (ref "C37") (pin "1") (pinfunction "1_1") (pintype "passive"))
      (node (ref "C38") (pin "1") (pinfunction "1_1") (pintype "passive"))
      (node (ref "C39") (pin "1") (pinfunction "1_1") (pintype "passive"))
      (node (ref "C40") (pin "+") (pinfunction "+_+") (pintype "passive"))
      (node (ref "C41") (pin "+") (pinfunction "+_+") (pintype "passive"))
      (node (ref "C42") (pin "+") (pinfunction "+_+") (pintype "passive"))
      (node (ref "C43") (pin "+") (pinfunction "+_+") (pintype "passive"))
      (node (ref "C44") (pin "+") (pinfunction "+_+") (pintype "passive"))
      (node (ref "C45") (pin "+") (pinfunction "+_+") (pintype "passive"))
      (node (ref "C47") (pin "1") (pinfunction "1_1") (pintype "passive"))
      (node (ref "C48") (pin "1") (pinfunction "1_1") (pintype "passive"))
      (node (ref "U$1") (pin "+V") (pinfunction "V+_+V") (pintype "bidirectional"))
    )
    (net (code "37") (name "Net-(U$1-V-)") (class "Default")
      (node (ref "C36") (pin "2") (pinfunction "2_2") (pintype "passive"))
      (node (ref "C37") (pin "2") (pinfunction "2_2") (pintype "passive"))
      (node (ref "C38") (pin "2") (pinfunction "2_2") (pintype "passive"))
      (node (ref "C39") (pin "2") (pinfunction "2_2") (pintype "passive"))
      (node (ref "C40") (pin "-") (pinfunction "-_-") (pintype "passive"))
      (node (ref "C41") (pin "-") (pinfunction "-_-") (pintype "passive"))
      (node (ref "C42") (pin "-") (pinfunction "-_-") (pintype "passive"))
      (node (ref "C43") (pin "-") (pinfunction "-_-") (pintype "passive"))
      (node (ref "C44") (pin "-") (pinfunction "-_-") (pintype "passive"))
      (node (ref "C45") (pin "-") (pinfunction "-_-") (pintype "passive"))
      (node (ref "C47") (pin "2") (pinfunction "2_2") (pintype "passive"))
      (node (ref "C48") (pin "2") (pinfunction "2_2") (pintype "passive"))
      (node (ref "U$1") (pin "-V") (pinfunction "V-_-V") (pintype "bidirectional"))
    )
    (net (code "38") (name "Net-(U$2-EN)") (class "Default")
      (node (ref "C52") (pin "+") (pinfunction "+_+") (pintype "passive"))
      (node (ref "C53") (pin "+") (pinfunction "+_+") (pintype "passive"))
      (node (ref "U$2") (pin "1") (pinfunction "IN_1") (pintype "bidirectional"))
      (node (ref "U$2") (pin "2") (pinfunction "IN_2") (pintype "bidirectional"))
      (node (ref "U$2") (pin "3") (pinfunction "IN_3") (pintype "bidirectional"))
      (node (ref "U$2") (pin "4") (pinfunction "EN_4") (pintype "bidirectional"))
      (node (ref "U$2") (pin "7") (pinfunction "PGFB_7") (pintype "bidirectional"))
    )
    (net (code "39") (name "Net-(U$2-GND)") (class "Default")
      (node (ref "C46") (pin "-") (pinfunction "-_-") (pintype "passive"))
      (node (ref "C49") (pin "-") (pinfunction "-_-") (pintype "passive"))
      (node (ref "C52") (pin "-") (pinfunction "-_-") (pintype "passive"))
      (node (ref "C53") (pin "-") (pinfunction "-_-") (pintype "passive"))
      (node (ref "R23") (pin "1") (pinfunction "1_1") (pintype "passive"))
      (node (ref "U$2") (pin "9") (pinfunction "GND_9") (pintype "bidirectional"))
      (node (ref "U$2") (pin "EXP") (pinfunction "PAD_EXP") (pintype "bidirectional"))
      (node (ref "U$4") (pin "5") (pinfunction "2_5") (pintype "passive"))
    )
    (net (code "40") (name "Net-(U$2-ILIM)") (class "Default")
      (node (ref "R23") (pin "2") (pinfunction "2_2") (pintype "passive"))
      (node (ref "U$2") (pin "6") (pinfunction "ILIM_6") (pintype "bidirectional"))
    )
    (net (code "41") (name "Net-(U$2-OUTS)") (class "Default")
      (node (ref "U$2") (pin "10") (pinfunction "OUTS_10") (pintype "bidirectional"))
      (node (ref "U$4") (pin "3") (pinfunction "1_3") (pintype "passive"))
    )
    (net (code "42") (name "Net-(U$2-SET)") (class "Default")
      (node (ref "C56") (pin "1") (pinfunction "1_1") (pintype "passive"))
      (node (ref "R26") (pin "2") (pinfunction "2_2") (pintype "passive"))
      (node (ref "U$2") (pin "8") (pinfunction "SET_8") (pintype "bidirectional"))
    )
    (net (code "43") (name "Net-(U$3-EN)") (class "Default")
      (node (ref "C54") (pin "+") (pinfunction "+_+") (pintype "passive"))
      (node (ref "C55") (pin "+") (pinfunction "+_+") (pintype "passive"))
      (node (ref "U$3") (pin "1") (pinfunction "IN_1") (pintype "bidirectional"))
      (node (ref "U$3") (pin "2") (pinfunction "IN_2") (pintype "bidirectional"))
      (node (ref "U$3") (pin "3") (pinfunction "IN_3") (pintype "bidirectional"))
      (node (ref "U$3") (pin "4") (pinfunction "EN_4") (pintype "bidirectional"))
      (node (ref "U$3") (pin "7") (pinfunction "PGFB_7") (pintype "bidirectional"))
    )
    (net (code "44") (name "Net-(U$3-GND)") (class "Default")
      (node (ref "C50") (pin "-") (pinfunction "-_-") (pintype "passive"))
      (node (ref "C51") (pin "-") (pinfunction "-_-") (pintype "passive"))
      (node (ref "C54") (pin "-") (pinfunction "-_-") (pintype "passive"))
      (node (ref "C55") (pin "-") (pinfunction "-_-") (pintype "passive"))
      (node (ref "C59") (pin "2") (pinfunction "2_2") (pintype "passive"))
      (node (ref "R28") (pin "1") (pinfunction "1_1") (pintype "passive"))
      (node (ref "U$3") (pin "9") (pinfunction "GND_9") (pintype "bidirectional"))
      (node (ref "U$3") (pin "EXP") (pinfunction "PAD_EXP") (pintype "bidirectional"))
      (node (ref "U$5") (pin "5") (pinfunction "2_5") (pintype "passive"))
    )
    (net (code "45") (name "Net-(U$3-ILIM)") (class "Default")
      (node (ref "R28") (pin "2") (pinfunction "2_2") (pintype "passive"))
      (node (ref "U$3") (pin "6") (pinfunction "ILIM_6") (pintype "bidirectional"))
    )
    (net (code "46") (name "Net-(U$3-OUTS)") (class "Default")
      (node (ref "U$3") (pin "10") (pinfunction "OUTS_10") (pintype "bidirectional"))
      (node (ref "U$5") (pin "3") (pinfunction "1_3") (pintype "passive"))
    )
    (net (code "47") (name "Net-(U$3-SET)") (class "Default")
      (node (ref "C57") (pin "1") (pinfunction "1_1") (pintype "passive"))
      (node (ref "R31") (pin "2") (pinfunction "2_2") (pintype "passive"))
      (node (ref "U$3") (pin "8") (pinfunction "SET_8") (pintype "bidirectional"))
    )
    (net (code "48") (name "Net-(U$4B-1)") (class "Default")
      (node (ref "C46") (pin "+") (pinfunction "+_+") (pintype "passive"))
      (node (ref "C49") (pin "+") (pinfunction "+_+") (pintype "passive"))
      (node (ref "U$2") (pin "11") (pinfunction "OUT_11") (pintype "bidirectional"))
      (node (ref "U$2") (pin "12") (pinfunction "OUT_12") (pintype "bidirectional"))
      (node (ref "U$4") (pin "4") (pinfunction "1_4") (pintype "passive"))
    )
    (net (code "49") (name "Net-(U$4B-2)") (class "Default")
      (node (ref "C56") (pin "2") (pinfunction "2_2") (pintype "passive"))
      (node (ref "R26") (pin "1") (pinfunction "1_1") (pintype "passive"))
      (node (ref "U$4") (pin "6") (pinfunction "2_6") (pintype "passive"))
    )
    (net (code "50") (name "Net-(U$5B-1)") (class "Default")
      (node (ref "C50") (pin "+") (pinfunction "+_+") (pintype "passive"))
      (node (ref "C51") (pin "+") (pinfunction "+_+") (pintype "passive"))
      (node (ref "C59") (pin "1") (pinfunction "1_1") (pintype "passive"))
      (node (ref "U$3") (pin "11") (pinfunction "OUT_11") (pintype "bidirectional"))
      (node (ref "U$3") (pin "12") (pinfunction "OUT_12") (pintype "bidirectional"))
      (node (ref "U$5") (pin "4") (pinfunction "1_4") (pintype "passive"))
    )
    (net (code "51") (name "Net-(U$5B-2)") (class "Default")
      (node (ref "C57") (pin "2") (pinfunction "2_2") (pintype "passive"))
      (node (ref "R31") (pin "1") (pinfunction "1_1") (pintype "passive"))
      (node (ref "U$5") (pin "6") (pinfunction "2_6") (pintype "passive"))
    )
    (net (code "52") (name "Net-(X5A-KL)") (class "Default")
      (node (ref "D15") (pin "A") (pinfunction "A_A") (pintype "passive"))
      (node (ref "R13") (pin "1") (pinfunction "1_1") (pintype "passive"))
      (node (ref "X5") (pin "1") (pinfunction "KL_1") (pintype "passive"))
    )
    (net (code "53") (name "Net-(X6B-KL)") (class "Default")
      (node (ref "C26") (pin "1") (pinfunction "1_1") (pintype "passive"))
      (node (ref "C28") (pin "2") (pinfunction "2_2") (pintype "passive"))
      (node (ref "D17") (pin "A") (pinfunction "A_A") (pintype "passive"))
      (node (ref "D19") (pin "C") (pinfunction "C_C") (pintype "passive"))
      (node (ref "X6") (pin "2") (pinfunction "KL_2") (pintype "passive"))
    )
    (net (code "54") (name "Net-(X7A-KL)") (class "Default")
      (node (ref "C25") (pin "1") (pinfunction "1_1") (pintype "passive"))
      (node (ref "C27") (pin "2") (pinfunction "2_2") (pintype "passive"))
      (node (ref "D16") (pin "A") (pinfunction "A_A") (pintype "passive"))
      (node (ref "D18") (pin "C") (pinfunction "C_C") (pintype "passive"))
      (node (ref "X7") (pin "1") (pinfunction "KL_1") (pintype "passive"))
    )
    (net (code "55") (name "V+") (class "Default")
      (node (ref "C16") (pin "+") (pinfunction "+_+") (pintype "passive"))
      (node (ref "C18") (pin "2") (pinfunction "2_2") (pintype "passive"))
      (node (ref "C20") (pin "2") (pinfunction "2_2") (pintype "passive"))
      (node (ref "C24") (pin "1") (pinfunction "1_1") (pintype "passive"))
      (node (ref "C6") (pin "+") (pinfunction "+_+") (pintype "passive"))
      (node (ref "D11") (pin "A") (pinfunction "A_A") (pintype "passive"))
      (node (ref "IC1") (pin "7") (pinfunction "V+_7") (pintype "power_in"))
      (node (ref "Q4") (pin "E") (pinfunction "E_E") (pintype "passive"))
      (node (ref "Q8") (pin "1") (pinfunction "D_1") (pintype "passive"))
      (node (ref "R13") (pin "2") (pinfunction "2_2") (pintype "passive"))
      (node (ref "R8") (pin "2") (pinfunction "2_2") (pintype "passive"))
      (node (ref "X1") (pin "1") (pinfunction "KL_1") (pintype "passive"))
      (node (ref "X2") (pin "1") (pinfunction "KL_1") (pintype "passive"))
      (node (ref "X3") (pin "1") (pinfunction "KL_1") (pintype "passive"))
      (node (ref "X4") (pin "1") (pinfunction "KL_1") (pintype "passive"))
    )
    (net (code "56") (name "V-") (class "Default")
      (node (ref "C10") (pin "-") (pinfunction "-_-") (pintype "passive"))
      (node (ref "C17") (pin "1") (pinfunction "1_1") (pintype "passive"))
      (node (ref "C19") (pin "1") (pinfunction "1_1") (pintype "passive"))
      (node (ref "C21") (pin "2") (pinfunction "2_2") (pintype "passive"))
      (node (ref "C3") (pin "-") (pinfunction "-_-") (pintype "passive"))
      (node (ref "D10") (pin "C") (pinfunction "C_C") (pintype "passive"))
      (node (ref "IC2") (pin "4") (pinfunction "V-_4") (pintype "power_in"))
      (node (ref "Q12") (pin "2") (pinfunction "G_2") (pintype "passive"))
      (node (ref "Q7") (pin "E") (pinfunction "E_E") (pintype "passive"))
      (node (ref "R12") (pin "1") (pinfunction "1_1") (pintype "passive"))
      (node (ref "R14") (pin "1") (pinfunction "1_1") (pintype "passive"))
      (node (ref "R9") (pin "1") (pinfunction "1_1") (pintype "passive"))
      (node (ref "X1") (pin "3") (pinfunction "KL_3") (pintype "passive"))
      (node (ref "X2") (pin "3") (pinfunction "KL_3") (pintype "passive"))
      (node (ref "X3") (pin "3") (pinfunction "KL_3") (pintype "passive"))
      (node (ref "X4") (pin "3") (pinfunction "KL_3") (pintype "passive"))
    )
    (net (code "57") (name "unconnected-(IC1-TRIM1-Pad1)") (class "Default")
      (node (ref "IC1") (pin "1") (pinfunction "TRIM1_1") (pintype "passive"))
    )
    (net (code "58") (name "unconnected-(IC1-TRIM2-Pad8)") (class "Default")
      (node (ref "IC1") (pin "8") (pinfunction "TRIM2_8") (pintype "passive"))
    )
    (net (code "59") (name "unconnected-(IC2-TRIM1-Pad1)") (class "Default")
      (node (ref "IC2") (pin "1") (pinfunction "TRIM1_1") (pintype "passive"))
    )
    (net (code "60") (name "unconnected-(IC2-TRIM2-Pad8)") (class "Default")
      (node (ref "IC2") (pin "8") (pinfunction "TRIM2_8") (pintype "passive"))
    )
    (net (code "61") (name "unconnected-(U$1-AC-L-PadAC{slash}L)") (class "Default")
      (node (ref "U$1") (pin "AC/L") (pinfunction "AC-L_AC/L") (pintype "bidirectional"))
    )
    (net (code "62") (name "unconnected-(U$1-AC-N-PadAC{slash}N)") (class "Default")
      (node (ref "U$1") (pin "AC/N") (pinfunction "AC-N_AC/N") (pintype "bidirectional"))
    )
    (net (code "63") (name "unconnected-(U$2-PG-Pad5)") (class "Default")
      (node (ref "U$2") (pin "5") (pinfunction "PG_5") (pintype "bidirectional"))
    )
    (net (code "64") (name "unconnected-(U$3-PG-Pad5)") (class "Default")
      (node (ref "U$3") (pin "5") (pinfunction "PG_5") (pintype "bidirectional"))
    )
  )
)
